# CAM-SCH.net
KiCad netlist of a schematic drawn in Altium Designer
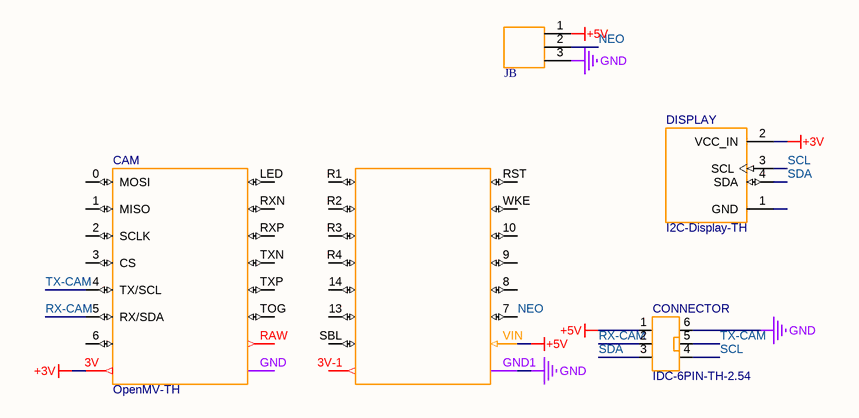
[diagram p0: CAM-SCH.SchDoc]

(export (version "E")
  (design (tool "Eeschema 10.0.6"))
  (components
    (comp (ref "CAM") (value "OpenMV-TH") (footprint "OpenMV-TH") (libsource (lib "RC") (part "OpenMV-TH")))
    (comp (ref "CONNECTOR")
      (value "IDC-6PIN-TH-2.54")
      (footprint "IDC-6PIN-TH-2.54")
      (libsource (lib "RC") (part "IDC-6PIN-TH-2.54"))
    )
    (comp (ref "DISPLAY")
      (value "I2C-Display-TH")
      (footprint "I2C-Display-TH")
      (libsource (lib "RC") (part "I2C-Display-TH"))
    )
    (comp (ref "JB")
      (value "3PIN")
      (footprint "3PIN")
      (description "2.54 Header")
      (libsource (lib "RC") (part "3PIN"))
    )
  )
  (nets
    (net (code "1") (name "+3V") (class "Default")
      (node (ref "CAM") (pin "3V") (pintype "output"))
      (node (ref "DISPLAY") (pin "2") (pinfunction "VCC_IN_2") (pintype "power_in"))
    )
    (net (code "2") (name "+5V") (class "Default")
      (node (ref "CAM") (pin "VIN") (pintype "input"))
      (node (ref "CONNECTOR") (pin "1") (pintype "passive"))
      (node (ref "JB") (pin "1") (pinfunction "01_1") (pintype "passive"))
    )
    (net (code "3") (name "/NEO") (class "Default")
      (node (ref "CAM") (pin "7") (pintype "bidirectional"))
      (node (ref "JB") (pin "2") (pinfunction "02_2") (pintype "passive"))
    )
    (net (code "4") (name "/RX-CAM") (class "Default")
      (node (ref "CAM") (pin "5") (pinfunction "RX/SDA_5") (pintype "bidirectional"))
      (node (ref "CONNECTOR") (pin "2") (pintype "passive"))
    )
    (net (code "5") (name "/SCL") (class "Default")
      (node (ref "CONNECTOR") (pin "4") (pintype "passive"))
      (node (ref "DISPLAY") (pin "3") (pinfunction "SCL_3") (pintype "input"))
    )
    (net (code "6") (name "/SDA") (class "Default")
      (node (ref "CONNECTOR") (pin "3") (pintype "passive"))
      (node (ref "DISPLAY") (pin "4") (pinfunction "SDA_4") (pintype "bidirectional"))
    )
    (net (code "7") (name "/TX-CAM") (class "Default")
      (node (ref "CAM") (pin "4") (pinfunction "TX/SCL_4") (pintype "bidirectional"))
      (node (ref "CONNECTOR") (pin "5") (pintype "passive"))
    )
    (net (code "8") (name "GND") (class "Default")
      (node (ref "CAM") (pin "GND1") (pintype "passive"))
      (node (ref "CONNECTOR") (pin "6") (pintype "passive"))
      (node (ref "JB") (pin "3") (pinfunction "03_3") (pintype "passive"))
    )
    (net (code "9") (name "unconnected-(CAM-CS-Pad3)") (class "Default")
      (node (ref "CAM") (pin "3") (pinfunction "CS_3") (pintype "bidirectional"))
    )
    (net (code "10") (name "unconnected-(CAM-MISO-Pad1)") (class "Default")
      (node (ref "CAM") (pin "1") (pinfunction "MISO_1") (pintype "bidirectional"))
    )
    (net (code "11") (name "unconnected-(CAM-MOSI-Pad0)") (class "Default")
      (node (ref "CAM") (pin "0") (pinfunction "MOSI_0") (pintype "bidirectional"))
    )
    (net (code "12") (name "unconnected-(CAM-Pad3V-1)") (class "Default")
      (node (ref "CAM") (pin "3V-1") (pintype "output"))
    )
    (net (code "13") (name "unconnected-(CAM-Pad6)") (class "Default")
      (node (ref "CAM") (pin "6") (pintype "bidirectional"))
    )
    (net (code "14") (name "unconnected-(CAM-Pad8)") (class "Default")
      (node (ref "CAM") (pin "8") (pintype "bidirectional"))
    )
    (net (code "15") (name "unconnected-(CAM-Pad9)") (class "Default")
      (node (ref "CAM") (pin "9") (pintype "bidirectional"))
    )
    (net (code "16") (name "unconnected-(CAM-Pad10)") (class "Default")
      (node (ref "CAM") (pin "10") (pintype "bidirectional"))
    )
    (net (code "17") (name "unconnected-(CAM-Pad13)") (class "Default")
      (node (ref "CAM") (pin "13") (pintype "bidirectional"))
    )
    (net (code "18") (name "unconnected-(CAM-Pad14)") (class "Default")
      (node (ref "CAM") (pin "14") (pintype "bidirectional"))
    )
    (net (code "19") (name "unconnected-(CAM-PadGND)") (class "Default")
      (node (ref "CAM") (pin "GND") (pintype "passive"))
    )
    (net (code "20") (name "unconnected-(CAM-PadLED)") (class "Default")
      (node (ref "CAM") (pin "LED") (pintype "bidirectional"))
    )
    (net (code "21") (name "unconnected-(CAM-PadR1)") (class "Default")
      (node (ref "CAM") (pin "R1") (pintype "bidirectional"))
    )
    (net (code "22") (name "unconnected-(CAM-PadR2)") (class "Default")
      (node (ref "CAM") (pin "R2") (pintype "bidirectional"))
    )
    (net (code "23") (name "unconnected-(CAM-PadR3)") (class "Default")
      (node (ref "CAM") (pin "R3") (pintype "bidirectional"))
    )
    (net (code "24") (name "unconnected-(CAM-PadR4)") (class "Default")
      (node (ref "CAM") (pin "R4") (pintype "bidirectional"))
    )
    (net (code "25") (name "unconnected-(CAM-PadRAW)") (class "Default")
      (node (ref "CAM") (pin "RAW") (pintype "output"))
    )
    (net (code "26") (name "unconnected-(CAM-PadRST)") (class "Default")
      (node (ref "CAM") (pin "RST") (pintype "bidirectional"))
    )
    (net (code "27") (name "unconnected-(CAM-PadRXN)") (class "Default")
      (node (ref "CAM") (pin "RXN") (pintype "bidirectional"))
    )
    (net (code "28") (name "unconnected-(CAM-PadRXP)") (class "Default")
      (node (ref "CAM") (pin "RXP") (pintype "bidirectional"))
    )
    (net (code "29") (name "unconnected-(CAM-PadSBL)") (class "Default")
      (node (ref "CAM") (pin "SBL") (pintype "bidirectional"))
    )
    (net (code "30") (name "unconnected-(CAM-PadTOG)") (class "Default")
      (node (ref "CAM") (pin "TOG") (pintype "bidirectional"))
    )
    (net (code "31") (name "unconnected-(CAM-PadTXN)") (class "Default")
      (node (ref "CAM") (pin "TXN") (pintype "bidirectional"))
    )
    (net (code "32") (name "unconnected-(CAM-PadTXP)") (class "Default")
      (node (ref "CAM") (pin "TXP") (pintype "bidirectional"))
    )
    (net (code "33") (name "unconnected-(CAM-PadWKE)") (class "Default")
      (node (ref "CAM") (pin "WKE") (pintype "bidirectional"))
    )
    (net (code "34") (name "unconnected-(CAM-SCLK-Pad2)") (class "Default")
      (node (ref "CAM") (pin "2") (pinfunction "SCLK_2") (pintype "bidirectional"))
    )
    (net (code "35") (name "unconnected-(DISPLAY-GND-Pad1)") (class "Default")
      (node (ref "DISPLAY") (pin "1") (pinfunction "GND_1") (pintype "power_in"))
    )
  )
)
